# Video_SW.net
KiCad netlist of a schematic drawn in EAGLE
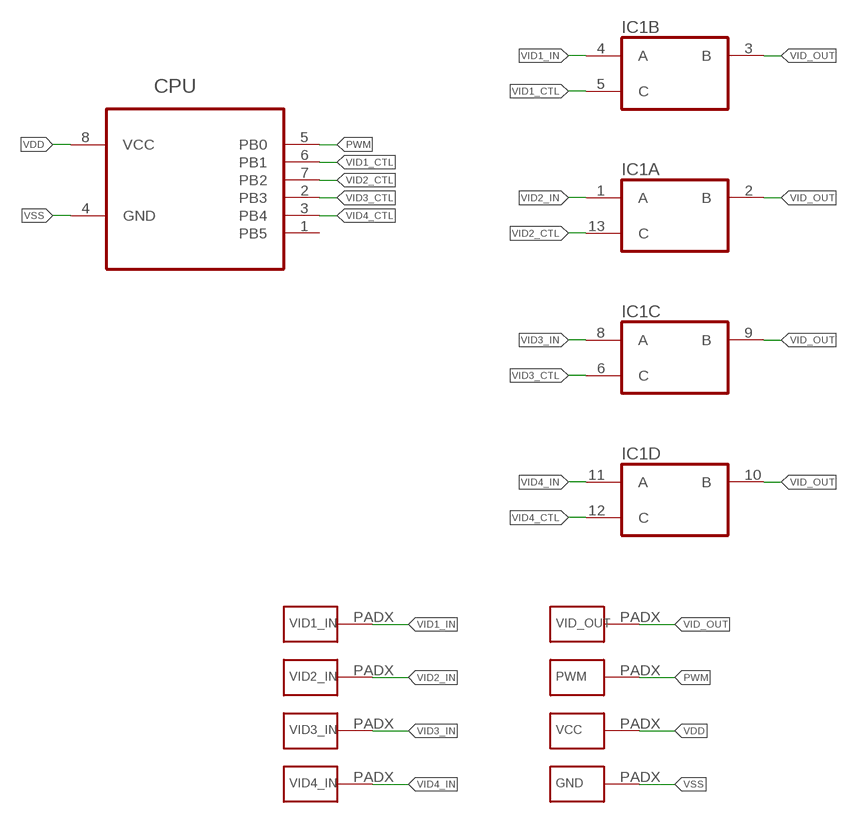
[diagram p0: schematic, sheet 1]

(export (version "E")
  (design (tool "Eeschema 10.0.6"))
  (components
    (comp (ref "CPU")
      (value "ATTINY85-20SU")
      (footprint "eagle-import:SOIC127P798X216-8N")
      (libsource (lib "eagle-import") (part "ATTINY85-20SU"))
    )
    (comp (ref "GND")
      (value "SOLDERPAD")
      (footprint "eagle-import:SOLDERPAD")
      (libsource (lib "eagle-import") (part "SOLDERPAD"))
    )
    (comp (ref "IC1")
      (value "4066D")
      (footprint "eagle-import:SO14")
      (libsource (lib "eagle-import") (part "4066D"))
    )
    (comp (ref "PWM")
      (value "SOLDERPAD")
      (footprint "eagle-import:SOLDERPAD")
      (libsource (lib "eagle-import") (part "SOLDERPAD"))
    )
    (comp (ref "VCC")
      (value "SOLDERPAD")
      (footprint "eagle-import:SOLDERPAD")
      (libsource (lib "eagle-import") (part "SOLDERPAD"))
    )
    (comp (ref "VID1_IN")
      (value "SOLDERPAD")
      (footprint "eagle-import:SOLDERPAD")
      (libsource (lib "eagle-import") (part "SOLDERPAD"))
    )
    (comp (ref "VID2_IN")
      (value "SOLDERPAD")
      (footprint "eagle-import:SOLDERPAD")
      (libsource (lib "eagle-import") (part "SOLDERPAD"))
    )
    (comp (ref "VID3_IN")
      (value "SOLDERPAD")
      (footprint "eagle-import:SOLDERPAD")
      (libsource (lib "eagle-import") (part "SOLDERPAD"))
    )
    (comp (ref "VID4_IN")
      (value "SOLDERPAD")
      (footprint "eagle-import:SOLDERPAD")
      (libsource (lib "eagle-import") (part "SOLDERPAD"))
    )
    (comp (ref "VID_OUT")
      (value "SOLDERPAD")
      (footprint "eagle-import:SOLDERPAD")
      (libsource (lib "eagle-import") (part "SOLDERPAD"))
    )
  )
  (nets
    (net (code "1") (name "PWM") (class "Default")
      (node (ref "CPU") (pin "5") (pinfunction "PB0_5") (pintype "bidirectional"))
      (node (ref "PWM") (pin "PADX") (pinfunction "P$1_PADX") (pintype "bidirectional"))
    )
    (net (code "2") (name "VDD") (class "Default")
      (node (ref "CPU") (pin "8") (pinfunction "VCC_8") (pintype "power_in"))
      (node (ref "VCC") (pin "PADX") (pinfunction "P$1_PADX") (pintype "bidirectional"))
    )
    (net (code "3") (name "VID1_CTL") (class "Default")
      (node (ref "CPU") (pin "6") (pinfunction "PB1_6") (pintype "bidirectional"))
      (node (ref "IC1") (pin "5") (pinfunction "C_5") (pintype "input"))
    )
    (net (code "4") (name "VID1_IN") (class "Default")
      (node (ref "IC1") (pin "4") (pinfunction "A_4") (pintype "tri_state"))
      (node (ref "VID1_IN") (pin "PADX") (pinfunction "P$1_PADX") (pintype "bidirectional"))
    )
    (net (code "5") (name "VID2_CTL") (class "Default")
      (node (ref "CPU") (pin "7") (pinfunction "PB2_7") (pintype "bidirectional"))
      (node (ref "IC1") (pin "13") (pinfunction "C_13") (pintype "input"))
    )
    (net (code "6") (name "VID2_IN") (class "Default")
      (node (ref "IC1") (pin "1") (pinfunction "A_1") (pintype "tri_state"))
      (node (ref "VID2_IN") (pin "PADX") (pinfunction "P$1_PADX") (pintype "bidirectional"))
    )
    (net (code "7") (name "VID3_CTL") (class "Default")
      (node (ref "CPU") (pin "2") (pinfunction "PB3_2") (pintype "bidirectional"))
      (node (ref "IC1") (pin "6") (pinfunction "C_6") (pintype "input"))
    )
    (net (code "8") (name "VID3_IN") (class "Default")
      (node (ref "IC1") (pin "8") (pinfunction "A_8") (pintype "tri_state"))
      (node (ref "VID3_IN") (pin "PADX") (pinfunction "P$1_PADX") (pintype "bidirectional"))
    )
    (net (code "9") (name "VID4_CTL") (class "Default")
      (node (ref "CPU") (pin "3") (pinfunction "PB4_3") (pintype "bidirectional"))
      (node (ref "IC1") (pin "12") (pinfunction "C_12") (pintype "input"))
    )
    (net (code "10") (name "VID4_IN") (class "Default")
      (node (ref "IC1") (pin "11") (pinfunction "A_11") (pintype "tri_state"))
      (node (ref "VID4_IN") (pin "PADX") (pinfunction "P$1_PADX") (pintype "bidirectional"))
    )
    (net (code "11") (name "VID_OUT") (class "Default")
      (node (ref "IC1") (pin "10") (pinfunction "B_10") (pintype "tri_state"))
      (node (ref "IC1") (pin "2") (pinfunction "B_2") (pintype "tri_state"))
      (node (ref "IC1") (pin "3") (pinfunction "B_3") (pintype "tri_state"))
      (node (ref "IC1") (pin "9") (pinfunction "B_9") (pintype "tri_state"))
      (node (ref "VID_OUT") (pin "PADX") (pinfunction "P$1_PADX") (pintype "bidirectional"))
    )
    (net (code "12") (name "VSS") (class "Default")
      (node (ref "CPU") (pin "4") (pinfunction "GND_4") (pintype "passive"))
      (node (ref "GND") (pin "PADX") (pinfunction "P$1_PADX") (pintype "bidirectional"))
    )
    (net (code "13") (name "unconnected-(CPU-PB5-Pad1)") (class "Default")
      (node (ref "CPU") (pin "1") (pinfunction "PB5_1") (pintype "bidirectional"))
    )
  )
)
